# Schematic.net
KiCad netlist of a schematic drawn in Altium Designer
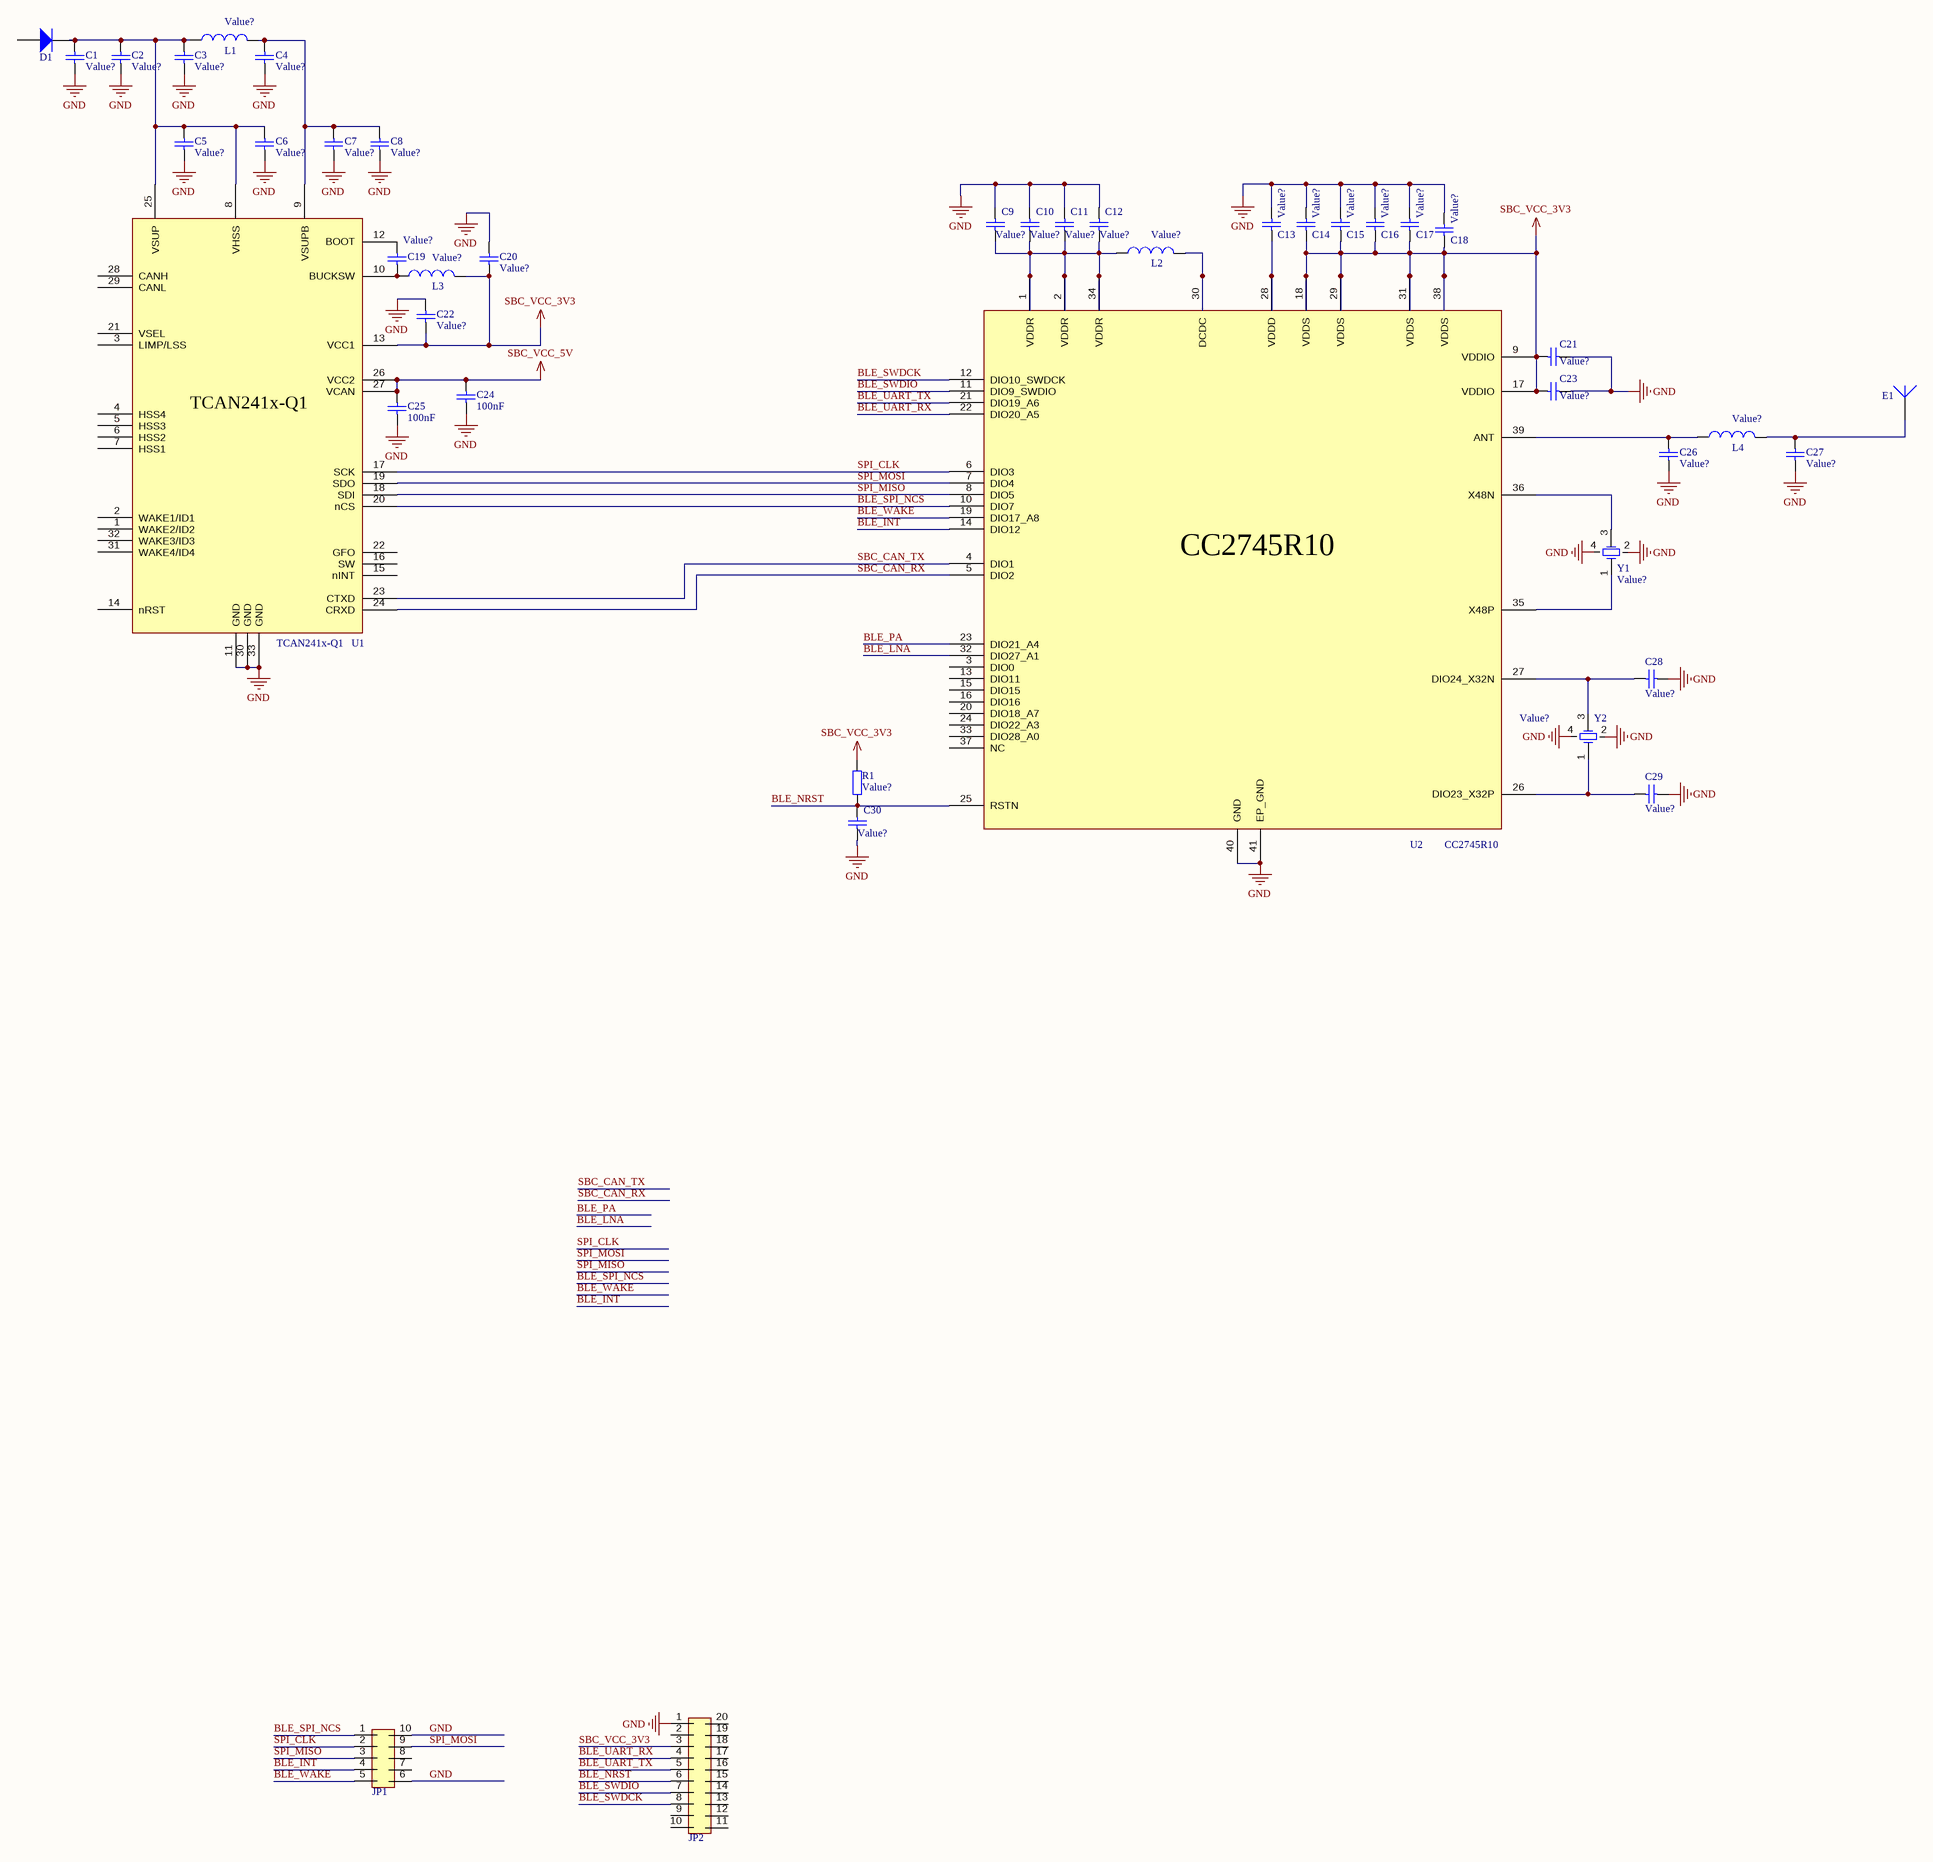
[diagram p0: Schematic.SchDoc]

(export (version "E")
  (design (tool "Eeschema 10.0.6"))
  (components
    (comp (ref "C1")
      (value "Value?")
      (description "Capacitor")
      (fields (field (name "Comment") "Cap"))
      (libsource (lib "Generic_Devices") (part "Cap"))
    )
    (comp (ref "C2")
      (value "Value?")
      (description "Capacitor")
      (fields (field (name "Comment") "Cap"))
      (libsource (lib "Generic_Devices") (part "Cap"))
    )
    (comp (ref "C3")
      (value "Value?")
      (description "Capacitor")
      (fields (field (name "Comment") "Cap"))
      (libsource (lib "Generic_Devices") (part "Cap"))
    )
    (comp (ref "C4")
      (value "Value?")
      (description "Capacitor")
      (fields (field (name "Comment") "Cap"))
      (libsource (lib "Generic_Devices") (part "Cap"))
    )
    (comp (ref "C5")
      (value "Value?")
      (description "Capacitor")
      (fields (field (name "Comment") "Cap"))
      (libsource (lib "Generic_Devices") (part "Cap"))
    )
    (comp (ref "C6")
      (value "Value?")
      (description "Capacitor")
      (fields (field (name "Comment") "Cap"))
      (libsource (lib "Generic_Devices") (part "Cap"))
    )
    (comp (ref "C7")
      (value "Value?")
      (description "Capacitor")
      (fields (field (name "Comment") "Cap"))
      (libsource (lib "Generic_Devices") (part "Cap"))
    )
    (comp (ref "C8")
      (value "Value?")
      (description "Capacitor")
      (fields (field (name "Comment") "Cap"))
      (libsource (lib "Generic_Devices") (part "Cap"))
    )
    (comp (ref "C9")
      (value "Value?")
      (description "Capacitor")
      (fields (field (name "Comment") "Cap"))
      (libsource (lib "Generic_Devices") (part "Cap"))
    )
    (comp (ref "C10")
      (value "Value?")
      (description "Capacitor")
      (fields (field (name "Comment") "Cap"))
      (libsource (lib "Generic_Devices") (part "Cap"))
    )
    (comp (ref "C11")
      (value "Value?")
      (description "Capacitor")
      (fields (field (name "Comment") "Cap"))
      (libsource (lib "Generic_Devices") (part "Cap"))
    )
    (comp (ref "C12")
      (value "Value?")
      (description "Capacitor")
      (fields (field (name "Comment") "Cap"))
      (libsource (lib "Generic_Devices") (part "Cap"))
    )
    (comp (ref "C13")
      (value "Value?")
      (description "Capacitor")
      (fields (field (name "Comment") "Cap"))
      (libsource (lib "Generic_Devices") (part "Cap"))
    )
    (comp (ref "C14")
      (value "Value?")
      (description "Capacitor")
      (fields (field (name "Comment") "Cap"))
      (libsource (lib "Generic_Devices") (part "Cap"))
    )
    (comp (ref "C15")
      (value "Value?")
      (description "Capacitor")
      (fields (field (name "Comment") "Cap"))
      (libsource (lib "Generic_Devices") (part "Cap"))
    )
    (comp (ref "C16")
      (value "Value?")
      (description "Capacitor")
      (fields (field (name "Comment") "Cap"))
      (libsource (lib "Generic_Devices") (part "Cap"))
    )
    (comp (ref "C17")
      (value "Value?")
      (description "Capacitor")
      (fields (field (name "Comment") "Cap"))
      (libsource (lib "Generic_Devices") (part "Cap"))
    )
    (comp (ref "C18")
      (value "Value?")
      (description "Capacitor")
      (fields (field (name "Comment") "Cap"))
      (libsource (lib "Generic_Devices") (part "Cap"))
    )
    (comp (ref "C19")
      (value "Value?")
      (description "Capacitor")
      (fields (field (name "Comment") "Cap"))
      (libsource (lib "Generic_Devices") (part "Cap"))
    )
    (comp (ref "C20")
      (value "Value?")
      (description "Capacitor")
      (fields (field (name "Comment") "Cap"))
      (libsource (lib "Generic_Devices") (part "Cap"))
    )
    (comp (ref "C21")
      (value "Value?")
      (description "Capacitor")
      (fields (field (name "Comment") "Cap"))
      (libsource (lib "Generic_Devices") (part "Cap"))
    )
    (comp (ref "C22")
      (value "Value?")
      (description "Capacitor")
      (fields (field (name "Comment") "Cap"))
      (libsource (lib "Generic_Devices") (part "Cap"))
    )
    (comp (ref "C23")
      (value "Value?")
      (description "Capacitor")
      (fields (field (name "Comment") "Cap"))
      (libsource (lib "Generic_Devices") (part "Cap"))
    )
    (comp (ref "C24")
      (value "100nF")
      (description "Capacitor")
      (fields (field (name "Comment") "Cap"))
      (libsource (lib "Generic_Devices") (part "Cap"))
    )
    (comp (ref "C25")
      (value "100nF")
      (description "Capacitor")
      (fields (field (name "Comment") "Cap"))
      (libsource (lib "Generic_Devices") (part "Cap"))
    )
    (comp (ref "C26")
      (value "Value?")
      (description "Capacitor")
      (fields (field (name "Comment") "Cap"))
      (libsource (lib "Generic_Devices") (part "Cap"))
    )
    (comp (ref "C27")
      (value "Value?")
      (description "Capacitor")
      (fields (field (name "Comment") "Cap"))
      (libsource (lib "Generic_Devices") (part "Cap"))
    )
    (comp (ref "C28")
      (value "Value?")
      (description "Capacitor")
      (fields (field (name "Comment") "Cap"))
      (libsource (lib "Generic_Devices") (part "Cap"))
    )
    (comp (ref "C29")
      (value "Value?")
      (description "Capacitor")
      (fields (field (name "Comment") "Cap"))
      (libsource (lib "Generic_Devices") (part "Cap"))
    )
    (comp (ref "C30")
      (value "Value?")
      (description "Capacitor")
      (fields (field (name "Comment") "Cap"))
      (libsource (lib "Generic_Devices") (part "Cap"))
    )
    (comp (ref "D1") (value "Diode") (libsource (lib "Generic_Devices") (part "Diode")))
    (comp (ref "E1") (value "Antenna") (libsource (lib "Generic_Devices") (part "Antenna")))
    (comp (ref "JP1")
      (value "Conn_02x05_Counter_Clockwise")
      (description "Connector 02x05 counter clockwise")
      (libsource (lib "Connector_Generic") (part "Conn_02x05_Counter_Clockwise"))
    )
    (comp (ref "JP2")
      (value "Conn_02x10_Counter_Clockwise")
      (description "Connector 02x10 counter clockwise")
      (libsource (lib "Connector_Generic") (part "Conn_02x10_Counter_Clockwise"))
    )
    (comp (ref "L1")
      (value "Value?")
      (description "Inductor")
      (libsource (lib "Generic_Devices") (part "Inductor"))
    )
    (comp (ref "L2")
      (value "Value?")
      (description "Inductor")
      (libsource (lib "Generic_Devices") (part "Inductor"))
    )
    (comp (ref "L3")
      (value "Value?")
      (description "Inductor")
      (libsource (lib "Generic_Devices") (part "Inductor"))
    )
    (comp (ref "L4")
      (value "Value?")
      (description "Inductor")
      (libsource (lib "Generic_Devices") (part "Inductor"))
    )
    (comp (ref "R1")
      (value "Value?")
      (description "Resistor")
      (fields (field (name "Comment") "Res"))
      (libsource (lib "Generic_Devices") (part "Res"))
    )
    (comp (ref "U1")
      (value "TCAN241x-Q1")
      (description "TCAN241x-Q1 Automotive CAN FD System Basis Chip SBC) with Integrated Buck Regulator and Watchdog")
      (libsource (lib "Interface_CAN_LIN") (part "TCAN241x-Q1"))
    )
    (comp (ref "U2") (value "CC2745R10") (libsource (lib "MCU_TI_CC27xx") (part "CC2745R10_Q1")))
    (comp (ref "Y1")
      (value "Value?")
      (description "Crystal 4 pins")
      (fields (field (name "Comment") "Crystal"))
      (libsource (lib "Generic_Devices") (part "Crystal"))
    )
    (comp (ref "Y2")
      (value "Value?")
      (description "Crystal 4 pins")
      (fields (field (name "Comment") "Crystal"))
      (libsource (lib "Generic_Devices") (part "Crystal"))
    )
  )
  (nets
    (net (code "1") (name "/BLE_INT") (class "Default")
      (node (ref "JP1") (pin "4") (pinfunction "4_4") (pintype "passive"))
      (node (ref "U2") (pin "14") (pinfunction "DIO12_14") (pintype "passive"))
    )
    (net (code "2") (name "/BLE_LNA") (class "Default")
      (node (ref "U2") (pin "32") (pinfunction "DIO27_A1_32") (pintype "passive"))
    )
    (net (code "3") (name "/BLE_NRST") (class "Default")
      (node (ref "C30") (pin "2") (pinfunction "2_2") (pintype "passive"))
      (node (ref "JP2") (pin "6") (pinfunction "6_6") (pintype "passive"))
      (node (ref "R1") (pin "1") (pinfunction "1_1") (pintype "passive"))
      (node (ref "U2") (pin "25") (pinfunction "RSTN_25") (pintype "passive"))
    )
    (net (code "4") (name "/BLE_PA") (class "Default")
      (node (ref "U2") (pin "23") (pinfunction "DIO21_A4_23") (pintype "passive"))
    )
    (net (code "5") (name "/BLE_SPI_NCS") (class "Default")
      (node (ref "JP1") (pin "1") (pinfunction "1_1") (pintype "passive"))
      (node (ref "U1") (pin "20") (pinfunction "nCS_20") (pintype "passive"))
      (node (ref "U2") (pin "10") (pinfunction "DIO7_10") (pintype "passive"))
    )
    (net (code "6") (name "/BLE_SWDCK") (class "Default")
      (node (ref "JP2") (pin "8") (pinfunction "8_8") (pintype "passive"))
      (node (ref "U2") (pin "12") (pinfunction "DIO10_SWDCK_12") (pintype "passive"))
    )
    (net (code "7") (name "/BLE_SWDIO") (class "Default")
      (node (ref "JP2") (pin "7") (pinfunction "7_7") (pintype "passive"))
      (node (ref "U2") (pin "11") (pinfunction "DIO9_SWDIO_11") (pintype "passive"))
    )
    (net (code "8") (name "/BLE_UART_RX") (class "Default")
      (node (ref "JP2") (pin "4") (pinfunction "4_4") (pintype "passive"))
      (node (ref "U2") (pin "22") (pinfunction "DIO20_A5_22") (pintype "passive"))
    )
    (net (code "9") (name "/BLE_UART_TX") (class "Default")
      (node (ref "JP2") (pin "5") (pinfunction "5_5") (pintype "passive"))
      (node (ref "U2") (pin "21") (pinfunction "DIO19_A6_21") (pintype "passive"))
    )
    (net (code "10") (name "/BLE_WAKE") (class "Default")
      (node (ref "JP1") (pin "5") (pinfunction "5_5") (pintype "passive"))
      (node (ref "U2") (pin "19") (pinfunction "DIO17_A8_19") (pintype "passive"))
    )
    (net (code "11") (name "/SBC_CAN_RX") (class "Default")
      (node (ref "U1") (pin "24") (pinfunction "CRXD_24") (pintype "passive"))
      (node (ref "U2") (pin "5") (pinfunction "DIO2_5") (pintype "passive"))
    )
    (net (code "12") (name "/SBC_CAN_TX") (class "Default")
      (node (ref "U1") (pin "23") (pinfunction "CTXD_23") (pintype "passive"))
      (node (ref "U2") (pin "4") (pinfunction "DIO1_4") (pintype "passive"))
    )
    (net (code "13") (name "/SPI_CLK") (class "Default")
      (node (ref "JP1") (pin "2") (pinfunction "2_2") (pintype "passive"))
      (node (ref "U1") (pin "17") (pinfunction "SCK_17") (pintype "passive"))
      (node (ref "U2") (pin "6") (pinfunction "DIO3_6") (pintype "passive"))
    )
    (net (code "14") (name "/SPI_MISO") (class "Default")
      (node (ref "JP1") (pin "3") (pinfunction "3_3") (pintype "passive"))
      (node (ref "U1") (pin "18") (pinfunction "SDI_18") (pintype "passive"))
      (node (ref "U2") (pin "8") (pinfunction "DIO5_8") (pintype "passive"))
    )
    (net (code "15") (name "/SPI_MOSI") (class "Default")
      (node (ref "JP1") (pin "9") (pinfunction "9_9") (pintype "passive"))
      (node (ref "U1") (pin "19") (pinfunction "SDO_19") (pintype "passive"))
      (node (ref "U2") (pin "7") (pinfunction "DIO4_7") (pintype "passive"))
    )
    (net (code "16") (name "GND") (class "Default")
      (node (ref "C1") (pin "1") (pinfunction "1_1") (pintype "passive"))
      (node (ref "C10") (pin "2") (pinfunction "2_2") (pintype "passive"))
      (node (ref "C11") (pin "2") (pinfunction "2_2") (pintype "passive"))
      (node (ref "C12") (pin "2") (pinfunction "2_2") (pintype "passive"))
      (node (ref "C13") (pin "2") (pinfunction "2_2") (pintype "passive"))
      (node (ref "C14") (pin "2") (pinfunction "2_2") (pintype "passive"))
      (node (ref "C15") (pin "2") (pinfunction "2_2") (pintype "passive"))
      (node (ref "C16") (pin "2") (pinfunction "2_2") (pintype "passive"))
      (node (ref "C17") (pin "2") (pinfunction "2_2") (pintype "passive"))
      (node (ref "C18") (pin "2") (pinfunction "2_2") (pintype "passive"))
      (node (ref "C2") (pin "1") (pinfunction "1_1") (pintype "passive"))
      (node (ref "C20") (pin "1") (pinfunction "1_1") (pintype "passive"))
      (node (ref "C21") (pin "2") (pinfunction "2_2") (pintype "passive"))
      (node (ref "C22") (pin "2") (pinfunction "2_2") (pintype "passive"))
      (node (ref "C23") (pin "2") (pinfunction "2_2") (pintype "passive"))
      (node (ref "C24") (pin "1") (pinfunction "1_1") (pintype "passive"))
      (node (ref "C25") (pin "1") (pinfunction "1_1") (pintype "passive"))
      (node (ref "C26") (pin "1") (pinfunction "1_1") (pintype "passive"))
      (node (ref "C27") (pin "1") (pinfunction "1_1") (pintype "passive"))
      (node (ref "C28") (pin "2") (pinfunction "2_2") (pintype "passive"))
      (node (ref "C29") (pin "2") (pinfunction "2_2") (pintype "passive"))
      (node (ref "C3") (pin "1") (pinfunction "1_1") (pintype "passive"))
      (node (ref "C30") (pin "1") (pinfunction "1_1") (pintype "passive"))
      (node (ref "C4") (pin "1") (pinfunction "1_1") (pintype "passive"))
      (node (ref "C5") (pin "1") (pinfunction "1_1") (pintype "passive"))
      (node (ref "C6") (pin "1") (pinfunction "1_1") (pintype "passive"))
      (node (ref "C7") (pin "1") (pinfunction "1_1") (pintype "passive"))
      (node (ref "C8") (pin "1") (pinfunction "1_1") (pintype "passive"))
      (node (ref "C9") (pin "2") (pinfunction "2_2") (pintype "passive"))
      (node (ref "JP1") (pin "10") (pinfunction "10_10") (pintype "passive"))
      (node (ref "JP1") (pin "6") (pinfunction "6_6") (pintype "passive"))
      (node (ref "JP2") (pin "1") (pinfunction "1_1") (pintype "passive"))
      (node (ref "U1") (pin "11") (pinfunction "GND_11") (pintype "passive"))
      (node (ref "U1") (pin "30") (pinfunction "GND_30") (pintype "passive"))
      (node (ref "U1") (pin "33") (pinfunction "GND_33") (pintype "passive"))
      (node (ref "U2") (pin "40") (pinfunction "GND_40") (pintype "passive"))
      (node (ref "U2") (pin "41") (pinfunction "EP_GND_41") (pintype "passive"))
      (node (ref "Y1") (pin "2") (pinfunction "GND_2") (pintype "passive"))
      (node (ref "Y1") (pin "4") (pinfunction "GND_4") (pintype "passive"))
      (node (ref "Y2") (pin "2") (pinfunction "GND_2") (pintype "passive"))
      (node (ref "Y2") (pin "4") (pinfunction "GND_4") (pintype "passive"))
    )
    (net (code "17") (name "Net-(C10-Pad1)") (class "Default")
      (node (ref "C10") (pin "1") (pinfunction "1_1") (pintype "passive"))
      (node (ref "C11") (pin "1") (pinfunction "1_1") (pintype "passive"))
      (node (ref "C12") (pin "1") (pinfunction "1_1") (pintype "passive"))
      (node (ref "C9") (pin "1") (pinfunction "1_1") (pintype "passive"))
      (node (ref "L2") (pin "1") (pinfunction "1_1") (pintype "passive"))
      (node (ref "U2") (pin "1") (pinfunction "VDDR_1") (pintype "passive"))
      (node (ref "U2") (pin "2") (pinfunction "VDDR_2") (pintype "passive"))
      (node (ref "U2") (pin "34") (pinfunction "VDDR_34") (pintype "passive"))
    )
    (net (code "18") (name "Net-(D1-K)") (class "Default")
      (node (ref "C1") (pin "2") (pinfunction "2_2") (pintype "passive"))
      (node (ref "C2") (pin "2") (pinfunction "2_2") (pintype "passive"))
      (node (ref "C3") (pin "2") (pinfunction "2_2") (pintype "passive"))
      (node (ref "C5") (pin "2") (pinfunction "2_2") (pintype "passive"))
      (node (ref "C6") (pin "2") (pinfunction "2_2") (pintype "passive"))
      (node (ref "D1") (pin "2") (pinfunction "K_2") (pintype "passive"))
      (node (ref "L1") (pin "1") (pinfunction "1_1") (pintype "passive"))
      (node (ref "U1") (pin "25") (pinfunction "VSUP_25") (pintype "passive"))
      (node (ref "U1") (pin "8") (pinfunction "VHSS_8") (pintype "passive"))
    )
    (net (code "19") (name "Net-(E1-A)") (class "Default")
      (node (ref "C27") (pin "2") (pinfunction "2_2") (pintype "passive"))
      (node (ref "E1") (pin "1") (pinfunction "A_1") (pintype "passive"))
      (node (ref "L4") (pin "2") (pinfunction "2_2") (pintype "passive"))
    )
    (net (code "20") (name "Net-(U1-BOOT)") (class "Default")
      (node (ref "C19") (pin "2") (pinfunction "2_2") (pintype "passive"))
      (node (ref "U1") (pin "12") (pinfunction "BOOT_12") (pintype "passive"))
    )
    (net (code "21") (name "Net-(U1-BUCKSW)") (class "Default")
      (node (ref "C19") (pin "1") (pinfunction "1_1") (pintype "passive"))
      (node (ref "L3") (pin "1") (pinfunction "1_1") (pintype "passive"))
      (node (ref "U1") (pin "10") (pinfunction "BUCKSW_10") (pintype "passive"))
    )
    (net (code "22") (name "Net-(U1-VSUPB)") (class "Default")
      (node (ref "C4") (pin "2") (pinfunction "2_2") (pintype "passive"))
      (node (ref "C7") (pin "2") (pinfunction "2_2") (pintype "passive"))
      (node (ref "C8") (pin "2") (pinfunction "2_2") (pintype "passive"))
      (node (ref "L1") (pin "2") (pinfunction "2_2") (pintype "passive"))
      (node (ref "U1") (pin "9") (pinfunction "VSUPB_9") (pintype "passive"))
    )
    (net (code "23") (name "Net-(U2-ANT)") (class "Default")
      (node (ref "C26") (pin "2") (pinfunction "2_2") (pintype "passive"))
      (node (ref "L4") (pin "1") (pinfunction "1_1") (pintype "passive"))
      (node (ref "U2") (pin "39") (pinfunction "ANT_39") (pintype "passive"))
    )
    (net (code "24") (name "Net-(U2-DCDC)") (class "Default")
      (node (ref "L2") (pin "2") (pinfunction "2_2") (pintype "passive"))
      (node (ref "U2") (pin "30") (pinfunction "DCDC_30") (pintype "passive"))
    )
    (net (code "25") (name "Net-(U2-DIO23_X32P)") (class "Default")
      (node (ref "C29") (pin "1") (pinfunction "1_1") (pintype "passive"))
      (node (ref "U2") (pin "26") (pinfunction "DIO23_X32P_26") (pintype "passive"))
      (node (ref "Y2") (pin "1") (pinfunction "OSC1_1") (pintype "passive"))
    )
    (net (code "26") (name "Net-(U2-DIO24_X32N)") (class "Default")
      (node (ref "C28") (pin "1") (pinfunction "1_1") (pintype "passive"))
      (node (ref "U2") (pin "27") (pinfunction "DIO24_X32N_27") (pintype "passive"))
      (node (ref "Y2") (pin "3") (pinfunction "OSC2_3") (pintype "passive"))
    )
    (net (code "27") (name "Net-(U2-VDDD)") (class "Default")
      (node (ref "C13") (pin "1") (pinfunction "1_1") (pintype "passive"))
      (node (ref "U2") (pin "28") (pinfunction "VDDD_28") (pintype "passive"))
    )
    (net (code "28") (name "Net-(U2-X48N)") (class "Default")
      (node (ref "U2") (pin "36") (pinfunction "X48N_36") (pintype "passive"))
      (node (ref "Y1") (pin "3") (pinfunction "OSC2_3") (pintype "passive"))
    )
    (net (code "29") (name "Net-(U2-X48P)") (class "Default")
      (node (ref "U2") (pin "35") (pinfunction "X48P_35") (pintype "passive"))
      (node (ref "Y1") (pin "1") (pinfunction "OSC1_1") (pintype "passive"))
    )
    (net (code "30") (name "SBC_VCC_3V3") (class "Default")
      (node (ref "C14") (pin "1") (pinfunction "1_1") (pintype "passive"))
      (node (ref "C15") (pin "1") (pinfunction "1_1") (pintype "passive"))
      (node (ref "C16") (pin "1") (pinfunction "1_1") (pintype "passive"))
      (node (ref "C17") (pin "1") (pinfunction "1_1") (pintype "passive"))
      (node (ref "C18") (pin "1") (pinfunction "1_1") (pintype "passive"))
      (node (ref "C20") (pin "2") (pinfunction "2_2") (pintype "passive"))
      (node (ref "C21") (pin "1") (pinfunction "1_1") (pintype "passive"))
      (node (ref "C22") (pin "1") (pinfunction "1_1") (pintype "passive"))
      (node (ref "C23") (pin "1") (pinfunction "1_1") (pintype "passive"))
      (node (ref "JP2") (pin "3") (pinfunction "3_3") (pintype "passive"))
      (node (ref "L3") (pin "2") (pinfunction "2_2") (pintype "passive"))
      (node (ref "R1") (pin "2") (pinfunction "2_2") (pintype "passive"))
      (node (ref "U1") (pin "13") (pinfunction "VCC1_13") (pintype "passive"))
      (node (ref "U2") (pin "17") (pinfunction "VDDIO_17") (pintype "passive"))
      (node (ref "U2") (pin "18") (pinfunction "VDDS_18") (pintype "passive"))
      (node (ref "U2") (pin "29") (pinfunction "VDDS_29") (pintype "passive"))
      (node (ref "U2") (pin "31") (pinfunction "VDDS_31") (pintype "passive"))
      (node (ref "U2") (pin "38") (pinfunction "VDDS_38") (pintype "passive"))
      (node (ref "U2") (pin "9") (pinfunction "VDDIO_9") (pintype "passive"))
    )
    (net (code "31") (name "SBC_VCC_5V") (class "Default")
      (node (ref "C24") (pin "2") (pinfunction "2_2") (pintype "passive"))
      (node (ref "C25") (pin "2") (pinfunction "2_2") (pintype "passive"))
      (node (ref "U1") (pin "26") (pinfunction "VCC2_26") (pintype "passive"))
      (node (ref "U1") (pin "27") (pinfunction "VCAN_27") (pintype "passive"))
    )
    (net (code "32") (name "unconnected-(D1-A-Pad1)") (class "Default")
      (node (ref "D1") (pin "1") (pinfunction "A_1") (pintype "passive"))
    )
    (net (code "33") (name "unconnected-(JP1-Pad7)") (class "Default")
      (node (ref "JP1") (pin "7") (pinfunction "7_7") (pintype "passive"))
    )
    (net (code "34") (name "unconnected-(JP1-Pad8)") (class "Default")
      (node (ref "JP1") (pin "8") (pinfunction "8_8") (pintype "passive"))
    )
    (net (code "35") (name "unconnected-(JP2-Pad2)") (class "Default")
      (node (ref "JP2") (pin "2") (pinfunction "2_2") (pintype "passive"))
    )
    (net (code "36") (name "unconnected-(JP2-Pad9)") (class "Default")
      (node (ref "JP2") (pin "9") (pinfunction "9_9") (pintype "passive"))
    )
    (net (code "37") (name "unconnected-(JP2-Pad10)") (class "Default")
      (node (ref "JP2") (pin "10") (pinfunction "10_10") (pintype "passive"))
    )
    (net (code "38") (name "unconnected-(JP2-Pad11)") (class "Default")
      (node (ref "JP2") (pin "11") (pinfunction "11_11") (pintype "passive"))
    )
    (net (code "39") (name "unconnected-(JP2-Pad12)") (class "Default")
      (node (ref "JP2") (pin "12") (pinfunction "12_12") (pintype "passive"))
    )
    (net (code "40") (name "unconnected-(JP2-Pad13)") (class "Default")
      (node (ref "JP2") (pin "13") (pinfunction "13_13") (pintype "passive"))
    )
    (net (code "41") (name "unconnected-(JP2-Pad14)") (class "Default")
      (node (ref "JP2") (pin "14") (pinfunction "14_14") (pintype "passive"))
    )
    (net (code "42") (name "unconnected-(JP2-Pad15)") (class "Default")
      (node (ref "JP2") (pin "15") (pinfunction "15_15") (pintype "passive"))
    )
    (net (code "43") (name "unconnected-(JP2-Pad16)") (class "Default")
      (node (ref "JP2") (pin "16") (pinfunction "16_16") (pintype "passive"))
    )
    (net (code "44") (name "unconnected-(JP2-Pad17)") (class "Default")
      (node (ref "JP2") (pin "17") (pinfunction "17_17") (pintype "passive"))
    )
    (net (code "45") (name "unconnected-(JP2-Pad18)") (class "Default")
      (node (ref "JP2") (pin "18") (pinfunction "18_18") (pintype "passive"))
    )
    (net (code "46") (name "unconnected-(JP2-Pad19)") (class "Default")
      (node (ref "JP2") (pin "19") (pinfunction "19_19") (pintype "passive"))
    )
    (net (code "47") (name "unconnected-(JP2-Pad20)") (class "Default")
      (node (ref "JP2") (pin "20") (pinfunction "20_20") (pintype "passive"))
    )
    (net (code "48") (name "unconnected-(U1-CANH-Pad28)") (class "Default")
      (node (ref "U1") (pin "28") (pinfunction "CANH_28") (pintype "passive"))
    )
    (net (code "49") (name "unconnected-(U1-CANL-Pad29)") (class "Default")
      (node (ref "U1") (pin "29") (pinfunction "CANL_29") (pintype "passive"))
    )
    (net (code "50") (name "unconnected-(U1-GFO-Pad22)") (class "Default")
      (node (ref "U1") (pin "22") (pinfunction "GFO_22") (pintype "passive"))
    )
    (net (code "51") (name "unconnected-(U1-HSS1-Pad7)") (class "Default")
      (node (ref "U1") (pin "7") (pinfunction "HSS1_7") (pintype "passive"))
    )
    (net (code "52") (name "unconnected-(U1-HSS2-Pad6)") (class "Default")
      (node (ref "U1") (pin "6") (pinfunction "HSS2_6") (pintype "passive"))
    )
    (net (code "53") (name "unconnected-(U1-HSS3-Pad5)") (class "Default")
      (node (ref "U1") (pin "5") (pinfunction "HSS3_5") (pintype "passive"))
    )
    (net (code "54") (name "unconnected-(U1-HSS4-Pad4)") (class "Default")
      (node (ref "U1") (pin "4") (pinfunction "HSS4_4") (pintype "passive"))
    )
    (net (code "55") (name "unconnected-(U1-LIMP{slash}LSS-Pad3)") (class "Default")
      (node (ref "U1") (pin "3") (pinfunction "LIMP/LSS_3") (pintype "passive"))
    )
    (net (code "56") (name "unconnected-(U1-SW-Pad16)") (class "Default")
      (node (ref "U1") (pin "16") (pinfunction "SW_16") (pintype "passive"))
    )
    (net (code "57") (name "unconnected-(U1-VSEL-Pad21)") (class "Default")
      (node (ref "U1") (pin "21") (pinfunction "VSEL_21") (pintype "passive"))
    )
    (net (code "58") (name "unconnected-(U1-WAKE1{slash}ID1-Pad2)") (class "Default")
      (node (ref "U1") (pin "2") (pinfunction "WAKE1/ID1_2") (pintype "passive"))
    )
    (net (code "59") (name "unconnected-(U1-WAKE2{slash}ID2-Pad1)") (class "Default")
      (node (ref "U1") (pin "1") (pinfunction "WAKE2/ID2_1") (pintype "passive"))
    )
    (net (code "60") (name "unconnected-(U1-WAKE3{slash}ID3-Pad32)") (class "Default")
      (node (ref "U1") (pin "32") (pinfunction "WAKE3/ID3_32") (pintype "passive"))
    )
    (net (code "61") (name "unconnected-(U1-WAKE4{slash}ID4-Pad31)") (class "Default")
      (node (ref "U1") (pin "31") (pinfunction "WAKE4/ID4_31") (pintype "passive"))
    )
    (net (code "62") (name "unconnected-(U1-nINT-Pad15)") (class "Default")
      (node (ref "U1") (pin "15") (pinfunction "nINT_15") (pintype "passive"))
    )
    (net (code "63") (name "unconnected-(U1-nRST-Pad14)") (class "Default")
      (node (ref "U1") (pin "14") (pinfunction "nRST_14") (pintype "passive"))
    )
    (net (code "64") (name "unconnected-(U2-DIO0-Pad3)") (class "Default")
      (node (ref "U2") (pin "3") (pinfunction "DIO0_3") (pintype "passive"))
    )
    (net (code "65") (name "unconnected-(U2-DIO11-Pad13)") (class "Default")
      (node (ref "U2") (pin "13") (pinfunction "DIO11_13") (pintype "passive"))
    )
    (net (code "66") (name "unconnected-(U2-DIO15-Pad15)") (class "Default")
      (node (ref "U2") (pin "15") (pinfunction "DIO15_15") (pintype "passive"))
    )
    (net (code "67") (name "unconnected-(U2-DIO16-Pad16)") (class "Default")
      (node (ref "U2") (pin "16") (pinfunction "DIO16_16") (pintype "passive"))
    )
    (net (code "68") (name "unconnected-(U2-DIO18_A7-Pad20)") (class "Default")
      (node (ref "U2") (pin "20") (pinfunction "DIO18_A7_20") (pintype "passive"))
    )
    (net (code "69") (name "unconnected-(U2-DIO22_A3-Pad24)") (class "Default")
      (node (ref "U2") (pin "24") (pinfunction "DIO22_A3_24") (pintype "passive"))
    )
    (net (code "70") (name "unconnected-(U2-DIO28_A0-Pad33)") (class "Default")
      (node (ref "U2") (pin "33") (pinfunction "DIO28_A0_33") (pintype "passive"))
    )
    (net (code "71") (name "unconnected-(U2-NC-Pad37)") (class "Default")
      (node (ref "U2") (pin "37") (pinfunction "NC_37") (pintype "passive"))
    )
  )
)
